# ps22.net
KiCad netlist of a schematic drawn in EAGLE
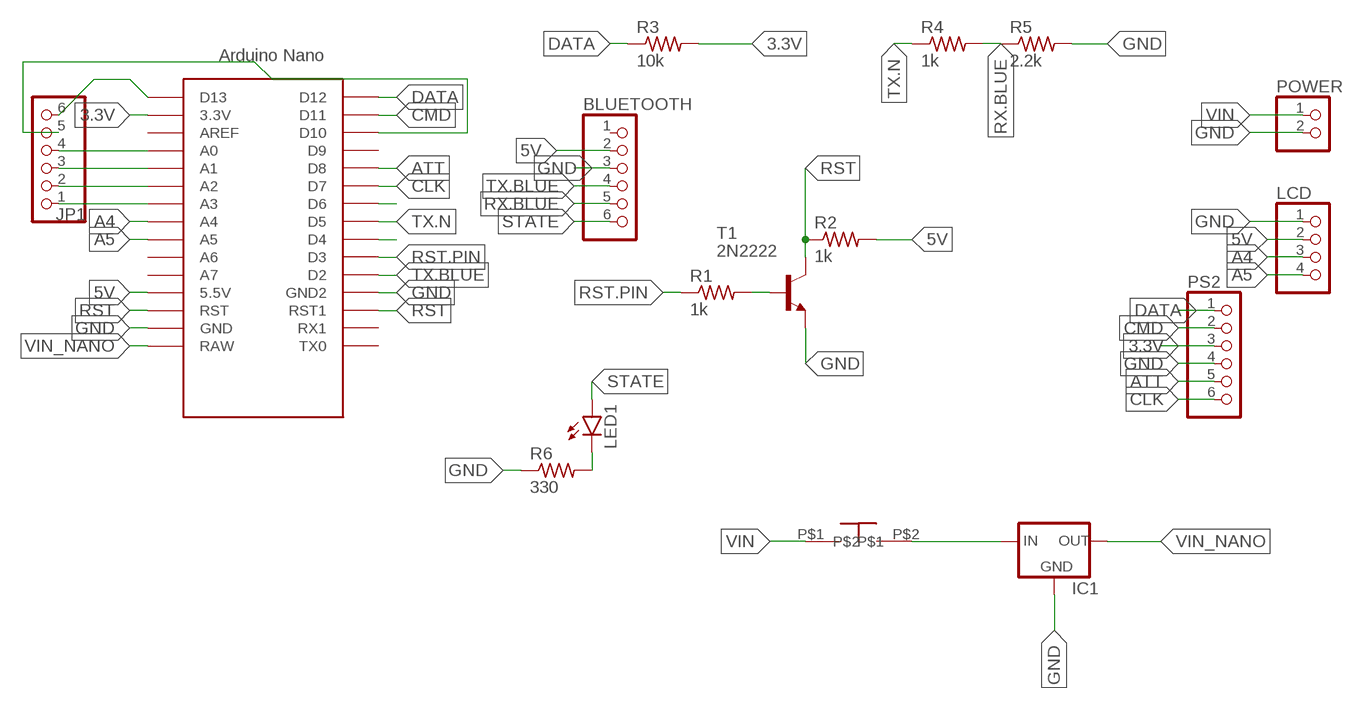
[diagram p0: schematic, sheet 1]

(export (version "E")
  (design (tool "Eeschema 10.0.6"))
  (components
    (comp (ref "BLUETOOTH")
      (value "PINHD-1X6")
      (footprint "eagle-import:1X06")
      (libsource (lib "eagle-import") (part "PINHD-1X6"))
    )
    (comp (ref "IC1")
      (value "78XXS")
      (footprint "eagle-import:78XXS")
      (libsource (lib "eagle-import") (part "78XXS"))
    )
    (comp (ref "JP1")
      (value "PINHD-1X6")
      (footprint "eagle-import:1X06")
      (libsource (lib "eagle-import") (part "PINHD-1X6"))
    )
    (comp (ref "LCD")
      (value "PINHD-1X4")
      (footprint "eagle-import:1X04")
      (libsource (lib "eagle-import") (part "PINHD-1X4"))
    )
    (comp (ref "LED1")
      (value "LED3MM")
      (footprint "eagle-import:LED3MM")
      (libsource (lib "eagle-import") (part "LED3MM"))
    )
    (comp (ref "POWER")
      (value "PINHD-1X2")
      (footprint "eagle-import:1X02")
      (libsource (lib "eagle-import") (part "PINHD-1X2"))
    )
    (comp (ref "PS2")
      (value "PINHD-1X6")
      (footprint "eagle-import:1X06")
      (libsource (lib "eagle-import") (part "PINHD-1X6"))
    )
    (comp (ref "R1")
      (value "1k")
      (footprint "eagle-import:0204_5")
      (libsource (lib "eagle-import") (part "R-US_0204/5"))
    )
    (comp (ref "R2")
      (value "1k")
      (footprint "eagle-import:0204_5")
      (libsource (lib "eagle-import") (part "R-US_0204/5"))
    )
    (comp (ref "R3")
      (value "10k")
      (footprint "eagle-import:0204_5")
      (libsource (lib "eagle-import") (part "R-US_0204/5"))
    )
    (comp (ref "R4")
      (value "1k")
      (footprint "eagle-import:0204_5")
      (libsource (lib "eagle-import") (part "R-US_0204/5"))
    )
    (comp (ref "R5")
      (value "2.2k")
      (footprint "eagle-import:0204_5")
      (libsource (lib "eagle-import") (part "R-US_0204/5"))
    )
    (comp (ref "R6")
      (value "330")
      (footprint "eagle-import:0204_5")
      (libsource (lib "eagle-import") (part "R-US_0204/5"))
    )
    (comp (ref "T1")
      (value "2N2222")
      (footprint "eagle-import:TO18")
      (libsource (lib "eagle-import") (part "2N2222"))
    )
    (comp (ref "U$1")
      (value "NANO")
      (footprint "eagle-import:NANO")
      (libsource (lib "eagle-import") (part "NANO"))
    )
    (comp (ref "U$2")
      (value "ON_OFF")
      (footprint "eagle-import:ON_OFF")
      (libsource (lib "eagle-import") (part "ON_OFF"))
    )
  )
  (nets
    (net (code "1") (name "3.3V") (class "Default")
      (node (ref "PS2") (pin "3") (pinfunction "3_3") (pintype "passive"))
      (node (ref "R3") (pin "2") (pinfunction "2_2") (pintype "passive"))
      (node (ref "U$1") (pin "3.3V") (pinfunction "3.3V_3.3V") (pintype "bidirectional"))
    )
    (net (code "2") (name "5V") (class "Default")
      (node (ref "BLUETOOTH") (pin "2") (pinfunction "2_2") (pintype "passive"))
      (node (ref "LCD") (pin "2") (pinfunction "2_2") (pintype "passive"))
      (node (ref "R2") (pin "2") (pinfunction "2_2") (pintype "passive"))
      (node (ref "U$1") (pin "5V") (pinfunction "5.5V_5V") (pintype "bidirectional"))
    )
    (net (code "3") (name "A4") (class "Default")
      (node (ref "LCD") (pin "3") (pinfunction "3_3") (pintype "passive"))
      (node (ref "U$1") (pin "A4") (pinfunction "A4_A4") (pintype "bidirectional"))
    )
    (net (code "4") (name "A5") (class "Default")
      (node (ref "LCD") (pin "4") (pinfunction "4_4") (pintype "passive"))
      (node (ref "U$1") (pin "A5") (pinfunction "A5_A5") (pintype "bidirectional"))
    )
    (net (code "5") (name "ATT") (class "Default")
      (node (ref "PS2") (pin "5") (pinfunction "5_5") (pintype "passive"))
      (node (ref "U$1") (pin "D8") (pinfunction "D8_D8") (pintype "bidirectional"))
    )
    (net (code "6") (name "CLK") (class "Default")
      (node (ref "PS2") (pin "6") (pinfunction "6_6") (pintype "passive"))
      (node (ref "U$1") (pin "D7") (pinfunction "D7_D7") (pintype "bidirectional"))
    )
    (net (code "7") (name "CMD") (class "Default")
      (node (ref "PS2") (pin "2") (pinfunction "2_2") (pintype "passive"))
      (node (ref "U$1") (pin "D11") (pinfunction "D11_D11") (pintype "bidirectional"))
    )
    (net (code "8") (name "DATA") (class "Default")
      (node (ref "PS2") (pin "1") (pinfunction "1_1") (pintype "passive"))
      (node (ref "R3") (pin "1") (pinfunction "1_1") (pintype "passive"))
      (node (ref "U$1") (pin "D12") (pinfunction "D12_D12") (pintype "bidirectional"))
    )
    (net (code "9") (name "GND") (class "Default")
      (node (ref "BLUETOOTH") (pin "3") (pinfunction "3_3") (pintype "passive"))
      (node (ref "IC1") (pin "GND") (pinfunction "GND_GND") (pintype "input"))
      (node (ref "LCD") (pin "1") (pinfunction "1_1") (pintype "passive"))
      (node (ref "POWER") (pin "2") (pinfunction "2_2") (pintype "passive"))
      (node (ref "PS2") (pin "4") (pinfunction "4_4") (pintype "passive"))
      (node (ref "R5") (pin "2") (pinfunction "2_2") (pintype "passive"))
      (node (ref "R6") (pin "1") (pinfunction "1_1") (pintype "passive"))
      (node (ref "T1") (pin "1") (pinfunction "E_1") (pintype "passive"))
      (node (ref "U$1") (pin "GND") (pinfunction "GND_GND") (pintype "bidirectional"))
      (node (ref "U$1") (pin "GND1") (pinfunction "GND2_GND1") (pintype "bidirectional"))
    )
    (net (code "10") (name "Net-(IC1-PadIN)") (class "Default")
      (node (ref "IC1") (pin "IN") (pinfunction "IN_IN") (pintype "input"))
      (node (ref "U$2") (pin "P$2") (pinfunction "P$2_P$2") (pintype "bidirectional"))
    )
    (net (code "11") (name "Net-(JP1-Pad1)") (class "Default")
      (node (ref "JP1") (pin "1") (pinfunction "1_1") (pintype "passive"))
      (node (ref "U$1") (pin "A3") (pinfunction "A3_A3") (pintype "bidirectional"))
    )
    (net (code "12") (name "Net-(JP1-Pad2)") (class "Default")
      (node (ref "JP1") (pin "2") (pinfunction "2_2") (pintype "passive"))
      (node (ref "U$1") (pin "A2") (pinfunction "A2_A2") (pintype "bidirectional"))
    )
    (net (code "13") (name "Net-(JP1-Pad3)") (class "Default")
      (node (ref "JP1") (pin "3") (pinfunction "3_3") (pintype "passive"))
      (node (ref "U$1") (pin "A1") (pinfunction "A1_A1") (pintype "bidirectional"))
    )
    (net (code "14") (name "Net-(JP1-Pad4)") (class "Default")
      (node (ref "JP1") (pin "4") (pinfunction "4_4") (pintype "passive"))
      (node (ref "U$1") (pin "A0") (pinfunction "A0_A0") (pintype "bidirectional"))
    )
    (net (code "15") (name "Net-(JP1-Pad5)") (class "Default")
      (node (ref "JP1") (pin "5") (pinfunction "5_5") (pintype "passive"))
      (node (ref "U$1") (pin "D10") (pinfunction "D10_D10") (pintype "bidirectional"))
    )
    (net (code "16") (name "Net-(JP1-Pad6)") (class "Default")
      (node (ref "JP1") (pin "6") (pinfunction "6_6") (pintype "passive"))
      (node (ref "U$1") (pin "D13") (pinfunction "D13_D13") (pintype "bidirectional"))
    )
    (net (code "17") (name "Net-(LED1-C)") (class "Default")
      (node (ref "LED1") (pin "K") (pinfunction "C_K") (pintype "passive"))
      (node (ref "R6") (pin "2") (pinfunction "2_2") (pintype "passive"))
    )
    (net (code "18") (name "Net-(T1-B)") (class "Default")
      (node (ref "R1") (pin "2") (pinfunction "2_2") (pintype "passive"))
      (node (ref "T1") (pin "2") (pinfunction "B_2") (pintype "passive"))
    )
    (net (code "19") (name "RST") (class "Default")
      (node (ref "R2") (pin "1") (pinfunction "1_1") (pintype "passive"))
      (node (ref "T1") (pin "3") (pinfunction "C_3") (pintype "passive"))
      (node (ref "U$1") (pin "RST") (pinfunction "RST_RST") (pintype "bidirectional"))
      (node (ref "U$1") (pin "RST1") (pinfunction "RST1_RST1") (pintype "bidirectional"))
    )
    (net (code "20") (name "RST.PIN") (class "Default")
      (node (ref "R1") (pin "1") (pinfunction "1_1") (pintype "passive"))
      (node (ref "U$1") (pin "D3") (pinfunction "D3_D3") (pintype "bidirectional"))
    )
    (net (code "21") (name "RX.BLUE") (class "Default")
      (node (ref "BLUETOOTH") (pin "5") (pinfunction "5_5") (pintype "passive"))
      (node (ref "R4") (pin "2") (pinfunction "2_2") (pintype "passive"))
      (node (ref "R5") (pin "1") (pinfunction "1_1") (pintype "passive"))
    )
    (net (code "22") (name "STATE") (class "Default")
      (node (ref "BLUETOOTH") (pin "6") (pinfunction "6_6") (pintype "passive"))
      (node (ref "LED1") (pin "A") (pinfunction "A_A") (pintype "passive"))
    )
    (net (code "23") (name "TX.BLUE") (class "Default")
      (node (ref "BLUETOOTH") (pin "4") (pinfunction "4_4") (pintype "passive"))
      (node (ref "U$1") (pin "D2") (pinfunction "D2_D2") (pintype "bidirectional"))
    )
    (net (code "24") (name "TX.N") (class "Default")
      (node (ref "R4") (pin "1") (pinfunction "1_1") (pintype "passive"))
      (node (ref "U$1") (pin "D5") (pinfunction "D5_D5") (pintype "bidirectional"))
    )
    (net (code "25") (name "VIN") (class "Default")
      (node (ref "POWER") (pin "1") (pinfunction "1_1") (pintype "passive"))
      (node (ref "U$2") (pin "P$1") (pinfunction "P$1_P$1") (pintype "bidirectional"))
    )
    (net (code "26") (name "VIN_NANO") (class "Default")
      (node (ref "IC1") (pin "OUT") (pinfunction "OUT_OUT") (pintype "passive"))
      (node (ref "U$1") (pin "RAW") (pinfunction "RAW_RAW") (pintype "bidirectional"))
    )
    (net (code "27") (name "unconnected-(BLUETOOTH-Pad1)") (class "Default")
      (node (ref "BLUETOOTH") (pin "1") (pinfunction "1_1") (pintype "passive"))
    )
    (net (code "28") (name "unconnected-(U$1-PadA6)") (class "Default")
      (node (ref "U$1") (pin "A6") (pinfunction "A6_A6") (pintype "bidirectional"))
    )
    (net (code "29") (name "unconnected-(U$1-PadA7)") (class "Default")
      (node (ref "U$1") (pin "A7") (pinfunction "A7_A7") (pintype "bidirectional"))
    )
    (net (code "30") (name "unconnected-(U$1-PadAREF)") (class "Default")
      (node (ref "U$1") (pin "AREF") (pinfunction "AREF_AREF") (pintype "bidirectional"))
    )
    (net (code "31") (name "unconnected-(U$1-PadD4)") (class "Default")
      (node (ref "U$1") (pin "D4") (pinfunction "D4_D4") (pintype "bidirectional"))
    )
    (net (code "32") (name "unconnected-(U$1-PadD6)") (class "Default")
      (node (ref "U$1") (pin "D6") (pinfunction "D6_D6") (pintype "bidirectional"))
    )
    (net (code "33") (name "unconnected-(U$1-PadD9)") (class "Default")
      (node (ref "U$1") (pin "D9") (pinfunction "D9_D9") (pintype "bidirectional"))
    )
    (net (code "34") (name "unconnected-(U$1-PadRX1)") (class "Default")
      (node (ref "U$1") (pin "RX1") (pinfunction "RX1_RX1") (pintype "bidirectional"))
    )
    (net (code "35") (name "unconnected-(U$1-PadTX0)") (class "Default")
      (node (ref "U$1") (pin "TX0") (pinfunction "TX0_TX0") (pintype "bidirectional"))
    )
  )
)
